# 6-Ethernet.net
KiCad netlist of a schematic drawn in Altium Designer
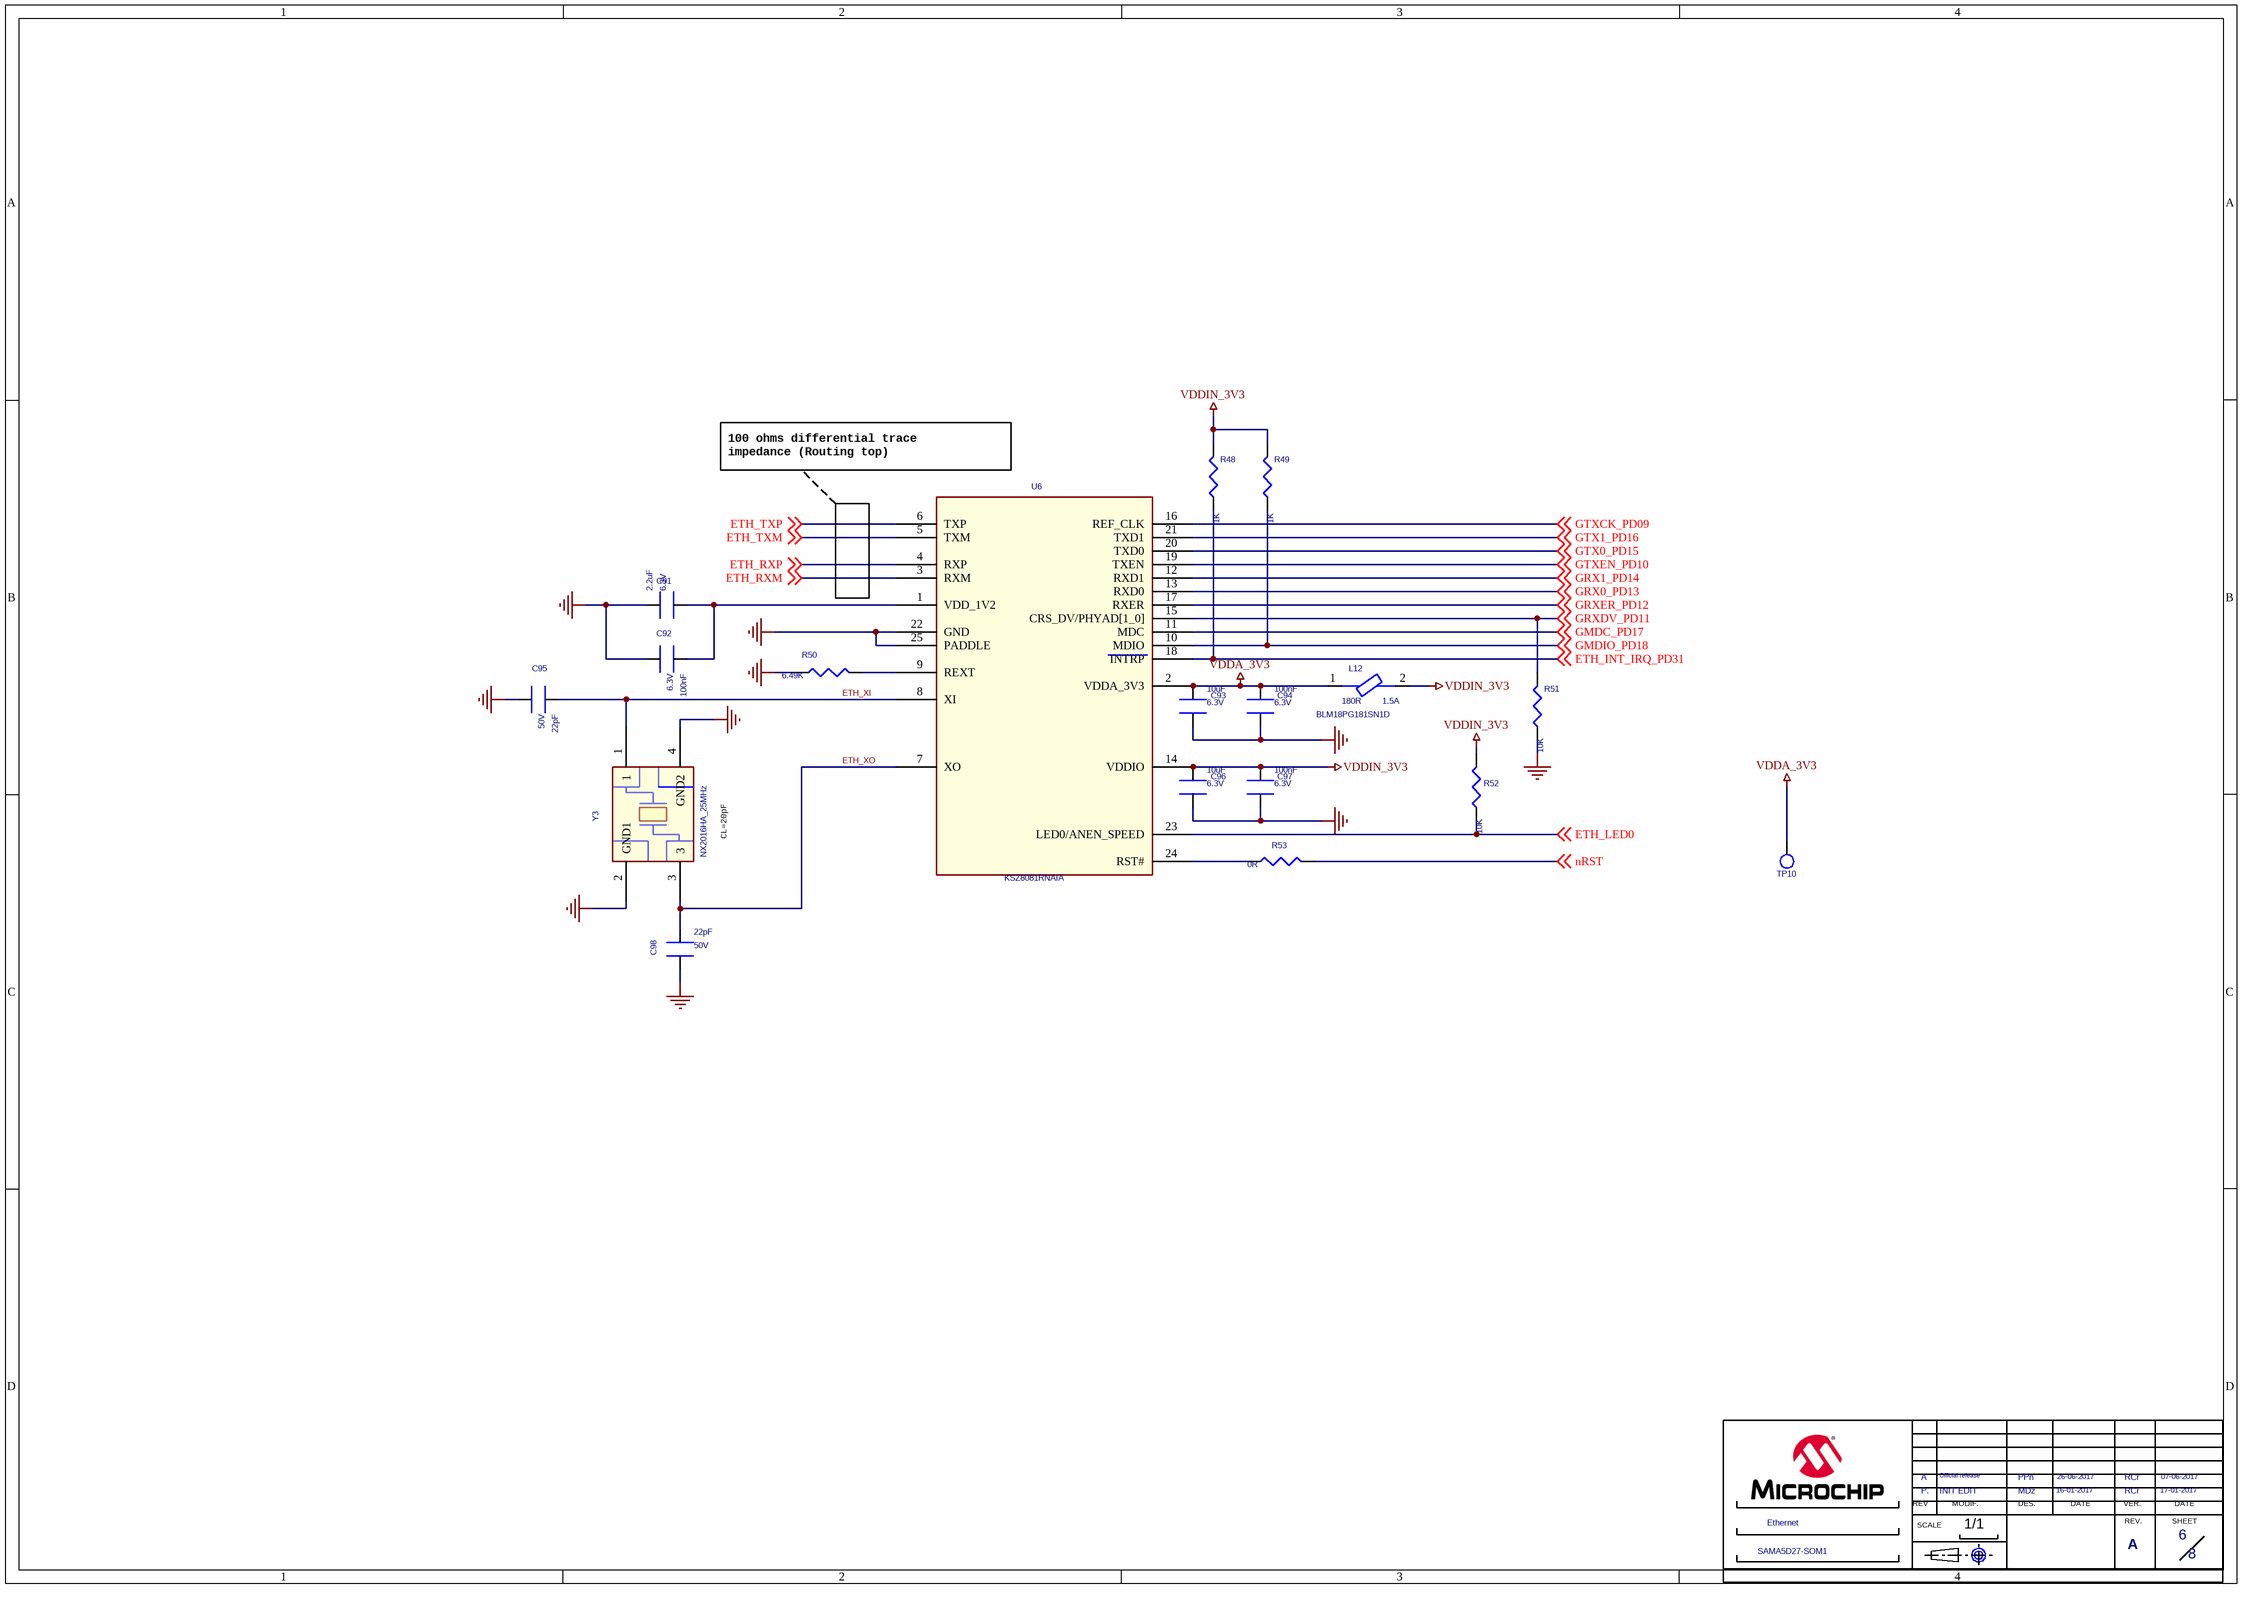
[diagram p0: 6-Ethernet.SchDoc]

(export (version "E")
  (design (tool "Eeschema 10.0.6"))
  (components
    (comp (ref "C91")
      (value "xpF x% xV")
      (footprint "C0402")
      (fields (field (name "VALEUR") "2.2uF") (field (name "TENSION") "6.3V") (field (name "HAUTEUR") "xmm"))
      (libsource (lib "*") (part "C0402-2.2uF-X5R-6.3V"))
    )
    (comp (ref "C92")
      (value "xpF x% xV")
      (footprint "C0201")
      (fields (field (name "VALEUR") "100nF") (field (name "TENSION") "6.3V") (field (name "HAUTEUR") "xmm"))
      (libsource (lib "*") (part "C0201-100nF-X5R-6.3V"))
    )
    (comp (ref "C93")
      (value "xpF x% xV")
      (footprint "C0402")
      (fields (field (name "TENSION") "6.3V") (field (name "VALEUR") "10uF") (field (name "HAUTEUR") "xmm"))
      (libsource (lib "*") (part "C0402-10uF-X5R-6.3V"))
    )
    (comp (ref "C94")
      (value "xpF x% xV")
      (footprint "C0201")
      (fields (field (name "VALEUR") "100nF") (field (name "TENSION") "6.3V") (field (name "HAUTEUR") "xmm"))
      (libsource (lib "*") (part "C0201-100nF-X5R-6.3V"))
    )
    (comp (ref "C95")
      (value "xpF x% xV")
      (footprint "C0201")
      (fields (field (name "TENSION") "50V") (field (name "VALEUR") "22pF") (field (name "HAUTEUR") "xmm"))
      (libsource (lib "*") (part "C0201-22pF-C0G-50V"))
    )
    (comp (ref "C96")
      (value "xpF x% xV")
      (footprint "C0402")
      (fields (field (name "TENSION") "6.3V") (field (name "VALEUR") "10uF") (field (name "HAUTEUR") "xmm"))
      (libsource (lib "*") (part "C0402-10uF-X5R-6.3V"))
    )
    (comp (ref "C97")
      (value "xpF x% xV")
      (footprint "C0201")
      (fields (field (name "VALEUR") "100nF") (field (name "TENSION") "6.3V") (field (name "HAUTEUR") "xmm"))
      (libsource (lib "*") (part "C0201-100nF-X5R-6.3V"))
    )
    (comp (ref "C98")
      (value "xpF x% xV")
      (footprint "C0201")
      (fields (field (name "TENSION") "50V") (field (name "VALEUR") "22pF") (field (name "HAUTEUR") "xmm"))
      (libsource (lib "*") (part "C0201-22pF-C0G-50V"))
    )
    (comp (ref "L12")
      (value "180R")
      (footprint "L0603_02")
      (fields
        (field (name "TOLERANCE") "25%")
        (field (name "PARTNUMBER") "MLZ1608N100L")
        (field (name "VALEUR") "BLM18PG181SN1D")
        (field (name "COURANT") "1.5A")
      )
      (libsource (lib "*") (part "BLM18PG181SN1D"))
    )
    (comp (ref "R48")
      (value "xR x% xW")
      (footprint "R0201")
      (fields (field (name "VALEUR") "1K") (field (name "TOLERANCE") "5%"))
      (libsource (lib "*") (part "R0201-1K-5%"))
    )
    (comp (ref "R49")
      (value "xR x% xW")
      (footprint "R0201")
      (fields (field (name "VALEUR") "1K") (field (name "TOLERANCE") "5%"))
      (libsource (lib "*") (part "R0201-1K-5%"))
    )
    (comp (ref "R50")
      (value "xR x% xW")
      (footprint "R0402")
      (fields (field (name "TOLERANCE") "1%") (field (name "VALEUR") "6.49K"))
      (libsource (lib "*") (part "R0402-6.49K-1%"))
    )
    (comp (ref "R51")
      (value "xR x% xW")
      (footprint "R0201")
      (fields (field (name "VALEUR") "10K") (field (name "TOLERANCE") "5%"))
      (libsource (lib "*") (part "R0201-10K-5%"))
    )
    (comp (ref "R52")
      (value "xR x% xW")
      (footprint "R0201")
      (fields (field (name "VALEUR") "10K") (field (name "TOLERANCE") "5%"))
      (libsource (lib "*") (part "R0201-10K-5%"))
    )
    (comp (ref "R53")
      (value "xR x% xW")
      (footprint "R0201")
      (fields (field (name "VALEUR") "0R") (field (name "TOLERANCE") "x%"))
      (libsource (lib "*") (part "R0201-0R"))
    )
    (comp (ref "TP10") (value "TP") (footprint "tp-cmsrond-1mm_02") (libsource (lib "*") (part "TP")))
    (comp (ref "U6")
      (value "KSZ8081RNAIA")
      (footprint "QFN24_01")
      (libsource (lib "*") (part "KSZ8081RNAIA"))
    )
    (comp (ref "Y3")
      (value "NX2016HA_25MHz")
      (footprint "QUARTZ-NX2016HA_01")
      (libsource (lib "*") (part "NX2016HA_25MHz"))
    )
  )
  (nets
    (net (code "1") (name "/ETH_XI") (class "Default")
      (node (ref "C95") (pin "2") (pinfunction "2_2") (pintype "passive"))
      (node (ref "U6") (pin "8") (pinfunction "XI_8") (pintype "passive"))
      (node (ref "Y3") (pin "1") (pinfunction "1_1") (pintype "passive"))
    )
    (net (code "2") (name "/ETH_XO") (class "Default")
      (node (ref "C98") (pin "2") (pinfunction "2_2") (pintype "passive"))
      (node (ref "U6") (pin "7") (pinfunction "XO_7") (pintype "passive"))
      (node (ref "Y3") (pin "3") (pinfunction "3_3") (pintype "passive"))
    )
    (net (code "3") (name "ETH_INT_IRQ_PD31") (class "Default")
      (node (ref "R48") (pin "1") (pinfunction "1_1") (pintype "passive"))
      (node (ref "U6") (pin "18") (pinfunction "INTRP_18") (pintype "passive"))
    )
    (net (code "4") (name "ETH_LED0") (class "Default")
      (node (ref "R52") (pin "1") (pinfunction "1_1") (pintype "passive"))
      (node (ref "U6") (pin "23") (pinfunction "LED0/ANEN_SPEED_23") (pintype "passive"))
    )
    (net (code "5") (name "ETH_RXM") (class "Default")
      (node (ref "U6") (pin "3") (pinfunction "RXM_3") (pintype "passive"))
    )
    (net (code "6") (name "ETH_RXP") (class "Default")
      (node (ref "U6") (pin "4") (pinfunction "RXP_4") (pintype "passive"))
    )
    (net (code "7") (name "ETH_TXM") (class "Default")
      (node (ref "U6") (pin "5") (pinfunction "TXM_5") (pintype "passive"))
    )
    (net (code "8") (name "ETH_TXP") (class "Default")
      (node (ref "U6") (pin "6") (pinfunction "TXP_6") (pintype "passive"))
    )
    (net (code "9") (name "GMDC_PD17") (class "Default")
      (node (ref "U6") (pin "11") (pinfunction "MDC_11") (pintype "passive"))
    )
    (net (code "10") (name "GMDIO_PD18") (class "Default")
      (node (ref "R49") (pin "1") (pinfunction "1_1") (pintype "passive"))
      (node (ref "U6") (pin "10") (pinfunction "MDIO_10") (pintype "passive"))
    )
    (net (code "11") (name "GND") (class "Default")
      (node (ref "C91") (pin "2") (pinfunction "2_2") (pintype "passive"))
      (node (ref "C92") (pin "1") (pinfunction "1_1") (pintype "passive"))
      (node (ref "C93") (pin "1") (pinfunction "1_1") (pintype "passive"))
      (node (ref "C94") (pin "1") (pinfunction "1_1") (pintype "passive"))
      (node (ref "C95") (pin "1") (pinfunction "1_1") (pintype "passive"))
      (node (ref "C96") (pin "1") (pinfunction "1_1") (pintype "passive"))
      (node (ref "C97") (pin "1") (pinfunction "1_1") (pintype "passive"))
      (node (ref "C98") (pin "1") (pinfunction "1_1") (pintype "passive"))
      (node (ref "R50") (pin "1") (pinfunction "1_1") (pintype "passive"))
      (node (ref "R51") (pin "1") (pinfunction "1_1") (pintype "passive"))
      (node (ref "U6") (pin "22") (pinfunction "GND_22") (pintype "passive"))
      (node (ref "U6") (pin "25") (pinfunction "PADDLE_25") (pintype "passive"))
      (node (ref "Y3") (pin "2") (pinfunction "GND1_2") (pintype "passive"))
      (node (ref "Y3") (pin "4") (pinfunction "GND2_4") (pintype "passive"))
    )
    (net (code "12") (name "GRX0_PD13") (class "Default")
      (node (ref "U6") (pin "13") (pinfunction "RXD0_13") (pintype "passive"))
    )
    (net (code "13") (name "GRX1_PD14") (class "Default")
      (node (ref "U6") (pin "12") (pinfunction "RXD1_12") (pintype "passive"))
    )
    (net (code "14") (name "GRXDV_PD11") (class "Default")
      (node (ref "R51") (pin "2") (pinfunction "2_2") (pintype "passive"))
      (node (ref "U6") (pin "15") (pinfunction "CRS_DV/PHYAD[1_0]_15") (pintype "passive"))
    )
    (net (code "15") (name "GRXER_PD12") (class "Default")
      (node (ref "U6") (pin "17") (pinfunction "RXER_17") (pintype "passive"))
    )
    (net (code "16") (name "GTX0_PD15") (class "Default")
      (node (ref "U6") (pin "20") (pinfunction "TXD0_20") (pintype "passive"))
    )
    (net (code "17") (name "GTX1_PD16") (class "Default")
      (node (ref "U6") (pin "21") (pinfunction "TXD1_21") (pintype "passive"))
    )
    (net (code "18") (name "GTXCK_PD09") (class "Default")
      (node (ref "U6") (pin "16") (pinfunction "REF_CLK_16") (pintype "passive"))
    )
    (net (code "19") (name "GTXEN_PD10") (class "Default")
      (node (ref "U6") (pin "19") (pinfunction "TXEN_19") (pintype "passive"))
    )
    (net (code "20") (name "Net-(U6-REXT)") (class "Default")
      (node (ref "R50") (pin "2") (pinfunction "2_2") (pintype "passive"))
      (node (ref "U6") (pin "9") (pinfunction "REXT_9") (pintype "passive"))
    )
    (net (code "21") (name "Net-(U6-RST#)") (class "Default")
      (node (ref "R53") (pin "1") (pinfunction "1_1") (pintype "passive"))
      (node (ref "U6") (pin "24") (pinfunction "RST#_24") (pintype "passive"))
    )
    (net (code "22") (name "Net-(U6-VDD_1V2)") (class "Default")
      (node (ref "C91") (pin "1") (pinfunction "1_1") (pintype "passive"))
      (node (ref "C92") (pin "2") (pinfunction "2_2") (pintype "passive"))
      (node (ref "U6") (pin "1") (pinfunction "VDD_1V2_1") (pintype "passive"))
    )
    (net (code "23") (name "VDDA_3V3") (class "Default")
      (node (ref "C93") (pin "2") (pinfunction "2_2") (pintype "passive"))
      (node (ref "C94") (pin "2") (pinfunction "2_2") (pintype "passive"))
      (node (ref "L12") (pin "1") (pinfunction "1_1") (pintype "passive"))
      (node (ref "TP10") (pin "1") (pinfunction "1_1") (pintype "passive"))
      (node (ref "U6") (pin "2") (pinfunction "VDDA_3V3_2") (pintype "passive"))
    )
    (net (code "24") (name "VDDIN_3V3") (class "Default")
      (node (ref "C96") (pin "2") (pinfunction "2_2") (pintype "passive"))
      (node (ref "C97") (pin "2") (pinfunction "2_2") (pintype "passive"))
      (node (ref "L12") (pin "2") (pinfunction "2_2") (pintype "passive"))
      (node (ref "R48") (pin "2") (pinfunction "2_2") (pintype "passive"))
      (node (ref "R49") (pin "2") (pinfunction "2_2") (pintype "passive"))
      (node (ref "R52") (pin "2") (pinfunction "2_2") (pintype "passive"))
      (node (ref "U6") (pin "14") (pinfunction "VDDIO_14") (pintype "passive"))
    )
    (net (code "25") (name "nRST") (class "Default")
      (node (ref "R53") (pin "2") (pinfunction "2_2") (pintype "passive"))
    )
  )
)
